# Sheet2.net
KiCad netlist of a schematic drawn in Altium Designer
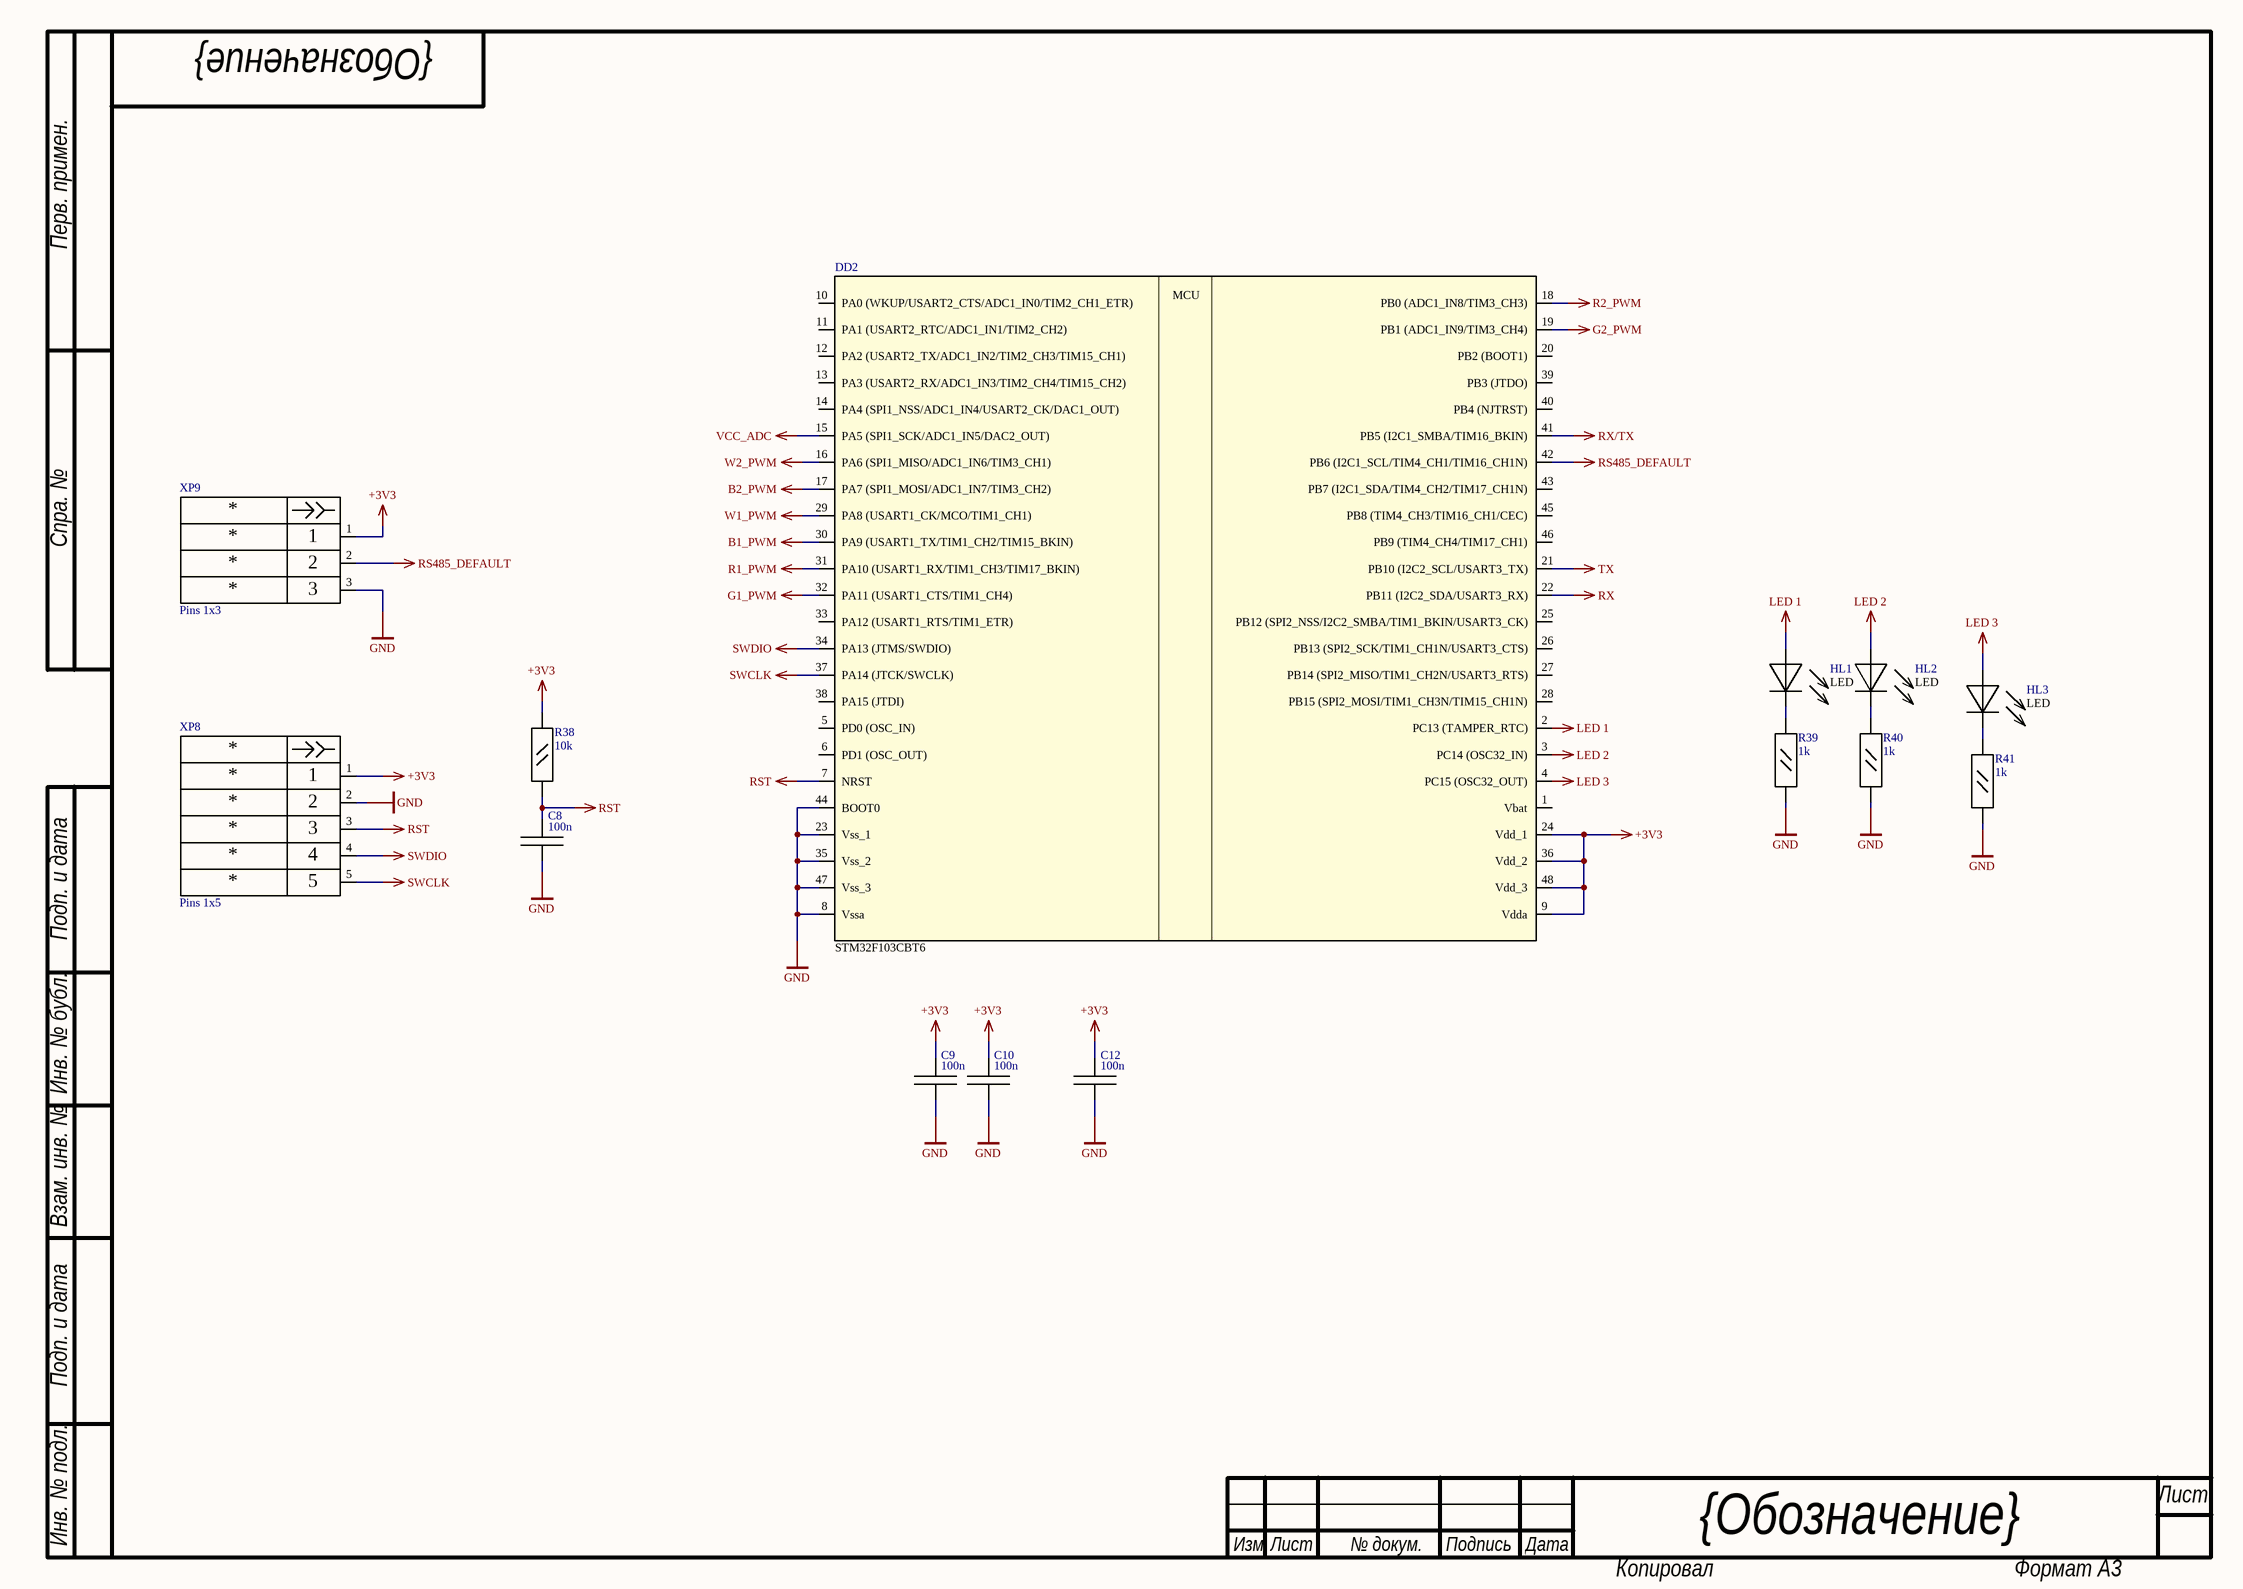
[diagram p0: Sheet2.SchDoc]

(export (version "E")
  (design (tool "Eeschema 10.0.6"))
  (components
    (comp (ref "C8")
      (value "100n")
      (footprint "Cap Ceramic 0805")
      (libsource (lib "Россыпь") (part "CerCap"))
    )
    (comp (ref "C9")
      (value "100n")
      (footprint "Cap Ceramic 0805")
      (libsource (lib "Россыпь") (part "CerCap"))
    )
    (comp (ref "C10")
      (value "100n")
      (footprint "Cap Ceramic 0805")
      (libsource (lib "Россыпь") (part "CerCap"))
    )
    (comp (ref "C12")
      (value "100n")
      (footprint "Cap Ceramic 0805")
      (libsource (lib "Россыпь") (part "CerCap"))
    )
    (comp (ref "DD2")
      (value "STM32F103CBT6")
      (footprint "TQFP48 S0.5")
      (libsource (lib "Россыпь") (part "STM32F100C4T6"))
    )
    (comp (ref "HL1") (value "LED") (footprint "LED 0805") (libsource (lib "Россыпь") (part "LED")))
    (comp (ref "HL2") (value "LED") (footprint "LED 0805") (libsource (lib "Россыпь") (part "LED")))
    (comp (ref "HL3") (value "LED") (footprint "LED 0805") (libsource (lib "Россыпь") (part "LED")))
    (comp (ref "R38")
      (value "10k")
      (footprint "Resistor 0805")
      (libsource (lib "Россыпь") (part "Resistor 0,125W"))
    )
    (comp (ref "R39")
      (value "1k")
      (footprint "Resistor 0805")
      (libsource (lib "Россыпь") (part "Resistor 0,125W"))
    )
    (comp (ref "R40")
      (value "1k")
      (footprint "Resistor 0805")
      (libsource (lib "Россыпь") (part "Resistor 0,125W"))
    )
    (comp (ref "R41")
      (value "1k")
      (footprint "Resistor 0805")
      (libsource (lib "Россыпь") (part "Resistor 0,125W"))
    )
    (comp (ref "XP8")
      (value "Pins 1x5")
      (footprint "Pins 1x5")
      (fields
        (field (name "NAME1") "*")
        (field (name "NAME") "*")
        (field (name "NAME2") "*")
        (field (name "NAME3") "*")
        (field (name "NAME4") "*")
        (field (name "NAME5") "*")
      )
      (libsource (lib "Россыпь") (part "Pins 1x5"))
    )
    (comp (ref "XP9")
      (value "Pins 1x3")
      (footprint "Pins 1x3")
      (fields
        (field (name "NAME1") "*")
        (field (name "NAME") "*")
        (field (name "NAME2") "*")
        (field (name "NAME3") "*")
      )
      (libsource (lib "Россыпь") (part "Pins 1x3"))
    )
  )
  (nets
    (net (code "1") (name "+3V3") (class "Default")
      (node (ref "C10") (pin "2") (pinfunction "2_2") (pintype "passive"))
      (node (ref "C12") (pin "2") (pinfunction "2_2") (pintype "passive"))
      (node (ref "C9") (pin "2") (pinfunction "2_2") (pintype "passive"))
      (node (ref "DD2") (pin "24") (pinfunction "Vdd_1_24") (pintype "passive"))
      (node (ref "DD2") (pin "36") (pinfunction "Vdd_2_36") (pintype "passive"))
      (node (ref "DD2") (pin "48") (pinfunction "Vdd_3_48") (pintype "passive"))
      (node (ref "DD2") (pin "9") (pinfunction "Vdda_9") (pintype "passive"))
      (node (ref "R38") (pin "1") (pinfunction "1_1") (pintype "passive"))
      (node (ref "XP8") (pin "1") (pinfunction "1_1") (pintype "passive"))
      (node (ref "XP9") (pin "1") (pinfunction "1_1") (pintype "passive"))
    )
    (net (code "2") (name "B1_PWM") (class "Default")
      (node (ref "DD2") (pin "30") (pinfunction "PA9_(USART1_TX/TIM1_CH2/TIM15_BKIN)_30") (pintype "passive"))
    )
    (net (code "3") (name "B2_PWM") (class "Default")
      (node (ref "DD2") (pin "17") (pinfunction "PA7_(SPI1_MOSI/ADC1_IN7/TIM3_CH2)_17") (pintype "passive"))
    )
    (net (code "4") (name "G1_PWM") (class "Default")
      (node (ref "DD2") (pin "32") (pinfunction "PA11_(USART1_CTS/TIM1_CH4)_32") (pintype "passive"))
    )
    (net (code "5") (name "G2_PWM") (class "Default")
      (node (ref "DD2") (pin "19") (pinfunction "PB1_(ADC1_IN9/TIM3_CH4)_19") (pintype "passive"))
    )
    (net (code "6") (name "GND") (class "Default")
      (node (ref "C10") (pin "1") (pinfunction "1_1") (pintype "passive"))
      (node (ref "C12") (pin "1") (pinfunction "1_1") (pintype "passive"))
      (node (ref "C8") (pin "1") (pinfunction "1_1") (pintype "passive"))
      (node (ref "C9") (pin "1") (pinfunction "1_1") (pintype "passive"))
      (node (ref "DD2") (pin "23") (pinfunction "Vss_1_23") (pintype "passive"))
      (node (ref "DD2") (pin "35") (pinfunction "Vss_2_35") (pintype "passive"))
      (node (ref "DD2") (pin "44") (pinfunction "BOOT0_44") (pintype "passive"))
      (node (ref "DD2") (pin "47") (pinfunction "Vss_3_47") (pintype "passive"))
      (node (ref "DD2") (pin "8") (pinfunction "Vssa_8") (pintype "passive"))
      (node (ref "R39") (pin "2") (pinfunction "2_2") (pintype "passive"))
      (node (ref "R40") (pin "2") (pinfunction "2_2") (pintype "passive"))
      (node (ref "R41") (pin "2") (pinfunction "2_2") (pintype "passive"))
      (node (ref "XP8") (pin "2") (pinfunction "2_2") (pintype "passive"))
      (node (ref "XP9") (pin "3") (pinfunction "3_3") (pintype "passive"))
    )
    (net (code "7") (name "LED 1") (class "Default")
      (node (ref "DD2") (pin "2") (pinfunction "PC13_(TAMPER_RTC)_2") (pintype "passive"))
      (node (ref "HL1") (pin "1") (pinfunction "A_1") (pintype "passive"))
    )
    (net (code "8") (name "LED 2") (class "Default")
      (node (ref "DD2") (pin "3") (pinfunction "PC14_(OSC32_IN)_3") (pintype "passive"))
      (node (ref "HL2") (pin "1") (pinfunction "A_1") (pintype "passive"))
    )
    (net (code "9") (name "LED 3") (class "Default")
      (node (ref "DD2") (pin "4") (pinfunction "PC15_(OSC32_OUT)_4") (pintype "passive"))
      (node (ref "HL3") (pin "1") (pinfunction "A_1") (pintype "passive"))
    )
    (net (code "10") (name "Net-(HL1-K)") (class "Default")
      (node (ref "HL1") (pin "2") (pinfunction "K_2") (pintype "passive"))
      (node (ref "R39") (pin "1") (pinfunction "1_1") (pintype "passive"))
    )
    (net (code "11") (name "Net-(HL2-K)") (class "Default")
      (node (ref "HL2") (pin "2") (pinfunction "K_2") (pintype "passive"))
      (node (ref "R40") (pin "1") (pinfunction "1_1") (pintype "passive"))
    )
    (net (code "12") (name "Net-(HL3-K)") (class "Default")
      (node (ref "HL3") (pin "2") (pinfunction "K_2") (pintype "passive"))
      (node (ref "R41") (pin "1") (pinfunction "1_1") (pintype "passive"))
    )
    (net (code "13") (name "R1_PWM") (class "Default")
      (node (ref "DD2") (pin "31") (pinfunction "PA10_(USART1_RX/TIM1_CH3/TIM17_BKIN)_31") (pintype "passive"))
    )
    (net (code "14") (name "R2_PWM") (class "Default")
      (node (ref "DD2") (pin "18") (pinfunction "PB0_(ADC1_IN8/TIM3_CH3)_18") (pintype "passive"))
    )
    (net (code "15") (name "RS485_DEFAULT") (class "Default")
      (node (ref "DD2") (pin "42") (pinfunction "PB6_(I2C1_SCL/TIM4_CH1/TIM16_CH1N)_42") (pintype "passive"))
      (node (ref "XP9") (pin "2") (pinfunction "2_2") (pintype "passive"))
    )
    (net (code "16") (name "RST") (class "Default")
      (node (ref "C8") (pin "2") (pinfunction "2_2") (pintype "passive"))
      (node (ref "DD2") (pin "7") (pinfunction "NRST_7") (pintype "passive"))
      (node (ref "R38") (pin "2") (pinfunction "2_2") (pintype "passive"))
      (node (ref "XP8") (pin "3") (pinfunction "3_3") (pintype "passive"))
    )
    (net (code "17") (name "RX") (class "Default")
      (node (ref "DD2") (pin "22") (pinfunction "PB11_(I2C2_SDA/USART3_RX)_22") (pintype "passive"))
    )
    (net (code "18") (name "RX{slash}TX") (class "Default")
      (node (ref "DD2") (pin "41") (pinfunction "PB5_(I2C1_SMBA/TIM16_BKIN)_41") (pintype "passive"))
    )
    (net (code "19") (name "SWCLK") (class "Default")
      (node (ref "DD2") (pin "37") (pinfunction "PA14_(JTCK/SWCLK)_37") (pintype "passive"))
      (node (ref "XP8") (pin "5") (pinfunction "5_5") (pintype "passive"))
    )
    (net (code "20") (name "SWDIO") (class "Default")
      (node (ref "DD2") (pin "34") (pinfunction "PA13_(JTMS/SWDIO)_34") (pintype "passive"))
      (node (ref "XP8") (pin "4") (pinfunction "4_4") (pintype "passive"))
    )
    (net (code "21") (name "TX") (class "Default")
      (node (ref "DD2") (pin "21") (pinfunction "PB10_(I2C2_SCL/USART3_TX)_21") (pintype "passive"))
    )
    (net (code "22") (name "VCC_ADC") (class "Default")
      (node (ref "DD2") (pin "15") (pinfunction "PA5_(SPI1_SCK/ADC1_IN5/DAC2_OUT)_15") (pintype "passive"))
    )
    (net (code "23") (name "W1_PWM") (class "Default")
      (node (ref "DD2") (pin "29") (pinfunction "PA8_(USART1_CK/MCO/TIM1_CH1)_29") (pintype "passive"))
    )
    (net (code "24") (name "W2_PWM") (class "Default")
      (node (ref "DD2") (pin "16") (pinfunction "PA6_(SPI1_MISO/ADC1_IN6/TIM3_CH1)_16") (pintype "passive"))
    )
    (net (code "25") (name "unconnected-(DD2-PA0_(WKUP{slash}USART2_CTS{slash}ADC1_IN0{slash}TIM2_CH1_ETR)-Pad10)") (class "Default")
      (node (ref "DD2") (pin "10") (pinfunction "PA0_(WKUP/USART2_CTS/ADC1_IN0/TIM2_CH1_ETR)_10") (pintype "passive"))
    )
    (net (code "26") (name "unconnected-(DD2-PA1_(USART2_RTC{slash}ADC1_IN1{slash}TIM2_CH2)-Pad11)") (class "Default")
      (node (ref "DD2") (pin "11") (pinfunction "PA1_(USART2_RTC/ADC1_IN1/TIM2_CH2)_11") (pintype "passive"))
    )
    (net (code "27") (name "unconnected-(DD2-PA2_(USART2_TX{slash}ADC1_IN2{slash}TIM2_CH3{slash}TIM15_CH1)-Pad12)") (class "Default")
      (node (ref "DD2") (pin "12") (pinfunction "PA2_(USART2_TX/ADC1_IN2/TIM2_CH3/TIM15_CH1)_12") (pintype "passive"))
    )
    (net (code "28") (name "unconnected-(DD2-PA3_(USART2_RX{slash}ADC1_IN3{slash}TIM2_CH4{slash}TIM15_CH2)-Pad13)") (class "Default")
      (node (ref "DD2") (pin "13") (pinfunction "PA3_(USART2_RX/ADC1_IN3/TIM2_CH4/TIM15_CH2)_13") (pintype "passive"))
    )
    (net (code "29") (name "unconnected-(DD2-PA4_(SPI1_NSS{slash}ADC1_IN4{slash}USART2_CK{slash}DAC1_OUT)-Pad14)") (class "Default")
      (node (ref "DD2") (pin "14") (pinfunction "PA4_(SPI1_NSS/ADC1_IN4/USART2_CK/DAC1_OUT)_14") (pintype "passive"))
    )
    (net (code "30") (name "unconnected-(DD2-PA12_(USART1_RTS{slash}TIM1_ETR)-Pad33)") (class "Default")
      (node (ref "DD2") (pin "33") (pinfunction "PA12_(USART1_RTS/TIM1_ETR)_33") (pintype "passive"))
    )
    (net (code "31") (name "unconnected-(DD2-PA15_(JTDI)-Pad38)") (class "Default")
      (node (ref "DD2") (pin "38") (pinfunction "PA15_(JTDI)_38") (pintype "passive"))
    )
    (net (code "32") (name "unconnected-(DD2-PB2_(BOOT1)-Pad20)") (class "Default")
      (node (ref "DD2") (pin "20") (pinfunction "PB2_(BOOT1)_20") (pintype "passive"))
    )
    (net (code "33") (name "unconnected-(DD2-PB3_(JTDO)-Pad39)") (class "Default")
      (node (ref "DD2") (pin "39") (pinfunction "PB3_(JTDO)_39") (pintype "passive"))
    )
    (net (code "34") (name "unconnected-(DD2-PB4_(NJTRST)-Pad40)") (class "Default")
      (node (ref "DD2") (pin "40") (pinfunction "PB4_(NJTRST)_40") (pintype "passive"))
    )
    (net (code "35") (name "unconnected-(DD2-PB7_(I2C1_SDA{slash}TIM4_CH2{slash}TIM17_CH1N)-Pad43)") (class "Default")
      (node (ref "DD2") (pin "43") (pinfunction "PB7_(I2C1_SDA/TIM4_CH2/TIM17_CH1N)_43") (pintype "passive"))
    )
    (net (code "36") (name "unconnected-(DD2-PB8_(TIM4_CH3{slash}TIM16_CH1{slash}CEC)-Pad45)") (class "Default")
      (node (ref "DD2") (pin "45") (pinfunction "PB8_(TIM4_CH3/TIM16_CH1/CEC)_45") (pintype "passive"))
    )
    (net (code "37") (name "unconnected-(DD2-PB9_(TIM4_CH4{slash}TIM17_CH1)-Pad46)") (class "Default")
      (node (ref "DD2") (pin "46") (pinfunction "PB9_(TIM4_CH4/TIM17_CH1)_46") (pintype "passive"))
    )
    (net (code "38") (name "unconnected-(DD2-PB12_(SPI2_NSS{slash}I2C2_SMBA{slash}TIM1_BKIN{slash}USART3_CK)-Pad25)") (class "Default")
      (node (ref "DD2") (pin "25") (pinfunction "PB12_(SPI2_NSS/I2C2_SMBA/TIM1_BKIN/USART3_CK)_25") (pintype "passive"))
    )
    (net (code "39") (name "unconnected-(DD2-PB13_(SPI2_SCK{slash}TIM1_CH1N{slash}USART3_CTS)-Pad26)") (class "Default")
      (node (ref "DD2") (pin "26") (pinfunction "PB13_(SPI2_SCK/TIM1_CH1N/USART3_CTS)_26") (pintype "passive"))
    )
    (net (code "40") (name "unconnected-(DD2-PB14_(SPI2_MISO{slash}TIM1_CH2N{slash}USART3_RTS)-Pad27)") (class "Default")
      (node (ref "DD2") (pin "27") (pinfunction "PB14_(SPI2_MISO/TIM1_CH2N/USART3_RTS)_27") (pintype "passive"))
    )
    (net (code "41") (name "unconnected-(DD2-PB15_(SPI2_MOSI{slash}TIM1_CH3N{slash}TIM15_CH1N)-Pad28)") (class "Default")
      (node (ref "DD2") (pin "28") (pinfunction "PB15_(SPI2_MOSI/TIM1_CH3N/TIM15_CH1N)_28") (pintype "passive"))
    )
    (net (code "42") (name "unconnected-(DD2-PD0_(OSC_IN)-Pad5)") (class "Default")
      (node (ref "DD2") (pin "5") (pinfunction "PD0_(OSC_IN)_5") (pintype "passive"))
    )
    (net (code "43") (name "unconnected-(DD2-PD1_(OSC_OUT)-Pad6)") (class "Default")
      (node (ref "DD2") (pin "6") (pinfunction "PD1_(OSC_OUT)_6") (pintype "passive"))
    )
    (net (code "44") (name "unconnected-(DD2-Vbat-Pad1)") (class "Default")
      (node (ref "DD2") (pin "1") (pinfunction "Vbat_1") (pintype "passive"))
    )
  )
)
